# AMU-S06-V00-CAN4.net
KiCad netlist of a schematic drawn in Altium Designer
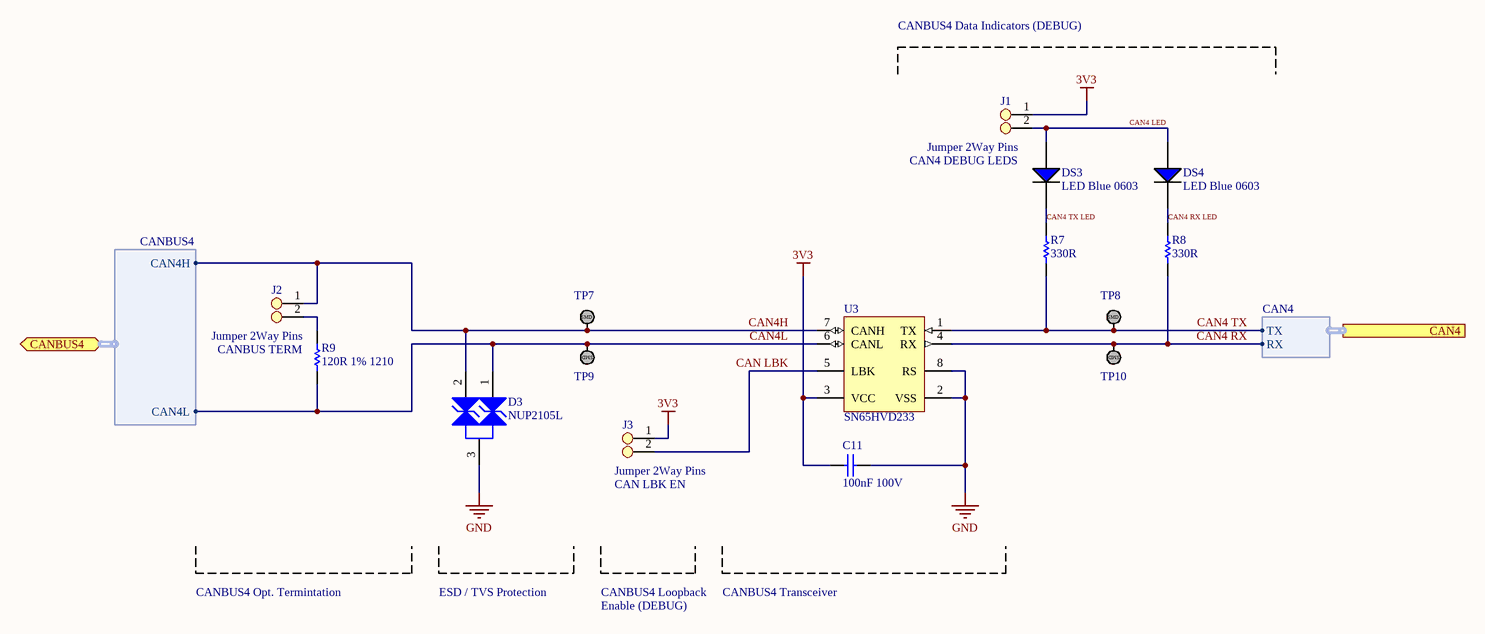
[diagram p0: AMU-S06-V00-CAN4.SchDoc]

(export (version "E")
  (design (tool "Eeschema 10.0.6"))
  (components
    (comp (ref "C11")
      (value "100nF 100V")
      (footprint "Cap_Ceramic_0603")
      (description "Capacitor, Ceramic, SMD, 100nF, 100V, 5%, X7R, 0603")
      (libsource (lib "StandardCapacitors") (part "100nF 100V 5% X7R 0603"))
    )
    (comp (ref "D3")
      (value "NUP2105L")
      (footprint "NUP2105L")
      (libsource (lib "QUTMS_CANLibrary") (part "NUP2105L"))
    )
    (comp (ref "DS3")
      (value "LED Blue 0603")
      (footprint "LED BLUE 0603")
      (libsource (lib "QUTMS_LEDLibrary") (part "LED BLUE 0603"))
    )
    (comp (ref "DS4")
      (value "LED Blue 0603")
      (footprint "LED BLUE 0603")
      (libsource (lib "QUTMS_LEDLibrary") (part "LED BLUE 0603"))
    )
    (comp (ref "J1")
      (value "Jumper 2Way Pins")
      (footprint "Jumper_2Way_Pin")
      (description "Jumper 2Way Side Pins")
      (libsource (lib "QUTMS_JumperLibrary") (part "Jumper 2Way Side Pins"))
    )
    (comp (ref "J2")
      (value "Jumper 2Way Pins")
      (footprint "Jumper_2Way_Pin")
      (description "Jumper 2Way Side Pins")
      (libsource (lib "QUTMS_JumperLibrary") (part "Jumper 2Way Side Pins"))
    )
    (comp (ref "J3")
      (value "Jumper 2Way Pins")
      (footprint "Jumper_2Way_Pin")
      (description "Jumper 2Way Side Pins")
      (libsource (lib "QUTMS_JumperLibrary") (part "Jumper 2Way Side Pins"))
    )
    (comp (ref "R7")
      (value "330R")
      (footprint "Res_ThinFilm_0603")
      (description "Resistor, SMD, 330R, 0.1W, 5%, 0603")
      (libsource (lib "StandardResistors") (part "330R 5% 0603"))
    )
    (comp (ref "R8")
      (value "330R")
      (footprint "Res_ThinFilm_0603")
      (description "Resistor, SMD, 330R, 0.1W, 5%, 0603")
      (libsource (lib "StandardResistors") (part "330R 5% 0603"))
    )
    (comp (ref "R9")
      (value "120R 1% 1210")
      (footprint "Res_ThinFilm_1210")
      (description "Resistor, SMD, 120R, 0.25W, 1%, 1210")
      (libsource (lib "StandardResistors") (part "120R 1% 1210"))
    )
    (comp (ref "TP7")
      (value "TestPoint_SMD")
      (footprint "TestPointSMD")
      (libsource (lib "StandardTest") (part "TestPoint_SMD"))
    )
    (comp (ref "TP8")
      (value "TestPoint_SMD")
      (footprint "TestPointSMD")
      (libsource (lib "StandardTest") (part "TestPoint_SMD"))
    )
    (comp (ref "TP9")
      (value "TestPoint_SMD")
      (footprint "TestPointSMD")
      (libsource (lib "StandardTest") (part "TestPoint_SMD"))
    )
    (comp (ref "TP10")
      (value "TestPoint_SMD")
      (footprint "TestPointSMD")
      (libsource (lib "StandardTest") (part "TestPoint_SMD"))
    )
    (comp (ref "U3")
      (value "SN65HVD233")
      (footprint "SN65HVD233DR")
      (libsource (lib "QUTMS_CANLibrary") (part "SN65HVD233"))
    )
  )
  (nets
    (net (code "3") (name "/CAN LBK") (class "Default")
      (node (ref "J3") (pin "2") (pinfunction "2_2") (pintype "passive"))
      (node (ref "U3") (pin "5") (pinfunction "LBK_5") (pintype "passive"))
    )
    (net (code "4") (name "/CAN4 LED") (class "Default")
      (node (ref "DS3") (pin "1") (pinfunction "A_1") (pintype "passive"))
      (node (ref "DS4") (pin "1") (pinfunction "A_1") (pintype "passive"))
      (node (ref "J1") (pin "2") (pinfunction "2_2") (pintype "passive"))
    )
    (net (code "5") (name "/CAN4 RX") (class "Default")
      (node (ref "R8") (pin "1") (pinfunction "1_1") (pintype "passive"))
      (node (ref "TP10") (pin "1") (pinfunction "1_1") (pintype "passive"))
      (node (ref "U3") (pin "4") (pinfunction "RX_4") (pintype "output"))
    )
    (net (code "6") (name "/CAN4 RX LED") (class "Default")
      (node (ref "DS4") (pin "2") (pinfunction "C_2") (pintype "passive"))
      (node (ref "R8") (pin "2") (pinfunction "2_2") (pintype "passive"))
    )
    (net (code "7") (name "/CAN4 TX") (class "Default")
      (node (ref "R7") (pin "1") (pinfunction "1_1") (pintype "passive"))
      (node (ref "TP8") (pin "1") (pinfunction "1_1") (pintype "passive"))
      (node (ref "U3") (pin "1") (pinfunction "TX_1") (pintype "input"))
    )
    (net (code "8") (name "/CAN4 TX LED") (class "Default")
      (node (ref "DS3") (pin "2") (pinfunction "C_2") (pintype "passive"))
      (node (ref "R7") (pin "2") (pinfunction "2_2") (pintype "passive"))
    )
    (net (code "9") (name "/CAN4H") (class "Default")
      (node (ref "D3") (pin "2") (pinfunction "2_2") (pintype "passive"))
      (node (ref "J2") (pin "1") (pinfunction "1_1") (pintype "passive"))
      (node (ref "TP7") (pin "1") (pinfunction "1_1") (pintype "passive"))
      (node (ref "U3") (pin "7") (pinfunction "CANH_7") (pintype "bidirectional"))
    )
    (net (code "10") (name "/CAN4L") (class "Default")
      (node (ref "D3") (pin "1") (pinfunction "1_1") (pintype "passive"))
      (node (ref "R9") (pin "1") (pinfunction "1_1") (pintype "passive"))
      (node (ref "TP9") (pin "1") (pinfunction "1_1") (pintype "passive"))
      (node (ref "U3") (pin "6") (pinfunction "CANL_6") (pintype "bidirectional"))
    )
    (net (code "13") (name "3V3") (class "Default")
      (node (ref "C11") (pin "2") (pinfunction "2_2") (pintype "passive"))
      (node (ref "J1") (pin "1") (pinfunction "1_1") (pintype "passive"))
      (node (ref "J3") (pin "1") (pinfunction "1_1") (pintype "passive"))
      (node (ref "U3") (pin "3") (pinfunction "VCC_3") (pintype "passive"))
    )
    (net (code "14") (name "GND") (class "Default")
      (node (ref "C11") (pin "1") (pinfunction "1_1") (pintype "passive"))
      (node (ref "D3") (pin "3") (pinfunction "3_3") (pintype "passive"))
      (node (ref "U3") (pin "2") (pinfunction "VSS_2") (pintype "passive"))
      (node (ref "U3") (pin "8") (pinfunction "RS_8") (pintype "passive"))
    )
    (net (code "15") (name "Net-(J2-Pad2)") (class "Default")
      (node (ref "J2") (pin "2") (pinfunction "2_2") (pintype "passive"))
      (node (ref "R9") (pin "2") (pinfunction "2_2") (pintype "passive"))
    )
  )
)
